# DSO_Clock.net
KiCad netlist of a schematic drawn in Altium Designer
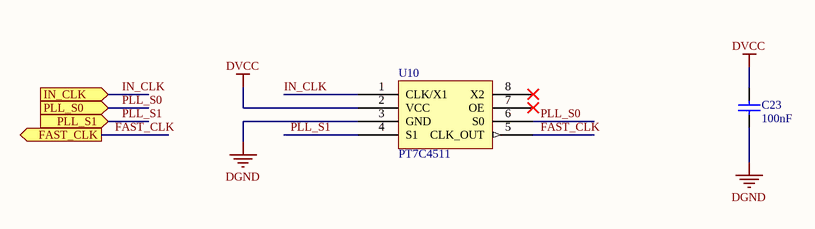
[diagram p0: DSO_Clock.SchDoc]

(export (version "E")
  (design (tool "Eeschema 10.0.6"))
  (components
    (comp (ref "C23")
      (value "100nF")
      (footprint "0805C")
      (description "Capacitor")
      (fields (field (name "REVIEWED BY") "RM - 2018/08/05"))
      (libsource (lib "DSO") (part "C"))
    )
    (comp (ref "U10")
      (value "PT7C4511")
      (footprint "SOIC-8")
      (description "PLL Clock Multiplier")
      (fields (field (name "REVIEWED BY") "RM - 2018/08/05"))
      (libsource (lib "DSO") (part "PT7C4511"))
    )
  )
  (nets
    (net (code "1") (name "/FAST_CLK") (class "Default")
      (node (ref "U10") (pin "5") (pinfunction "CLK_OUT_5") (pintype "output"))
    )
    (net (code "2") (name "/IN_CLK") (class "Default")
      (node (ref "U10") (pin "1") (pinfunction "CLK/X1_1") (pintype "passive"))
    )
    (net (code "3") (name "/PLL_S0") (class "Default")
      (node (ref "U10") (pin "6") (pinfunction "S0_6") (pintype "passive"))
    )
    (net (code "4") (name "/PLL_S1") (class "Default")
      (node (ref "U10") (pin "4") (pinfunction "S1_4") (pintype "passive"))
    )
    (net (code "5") (name "DGND") (class "Default")
      (node (ref "C23") (pin "2") (pinfunction "2_2") (pintype "passive"))
      (node (ref "U10") (pin "3") (pinfunction "GND_3") (pintype "passive"))
    )
    (net (code "6") (name "DVCC") (class "Default")
      (node (ref "C23") (pin "1") (pinfunction "1_1") (pintype "passive"))
      (node (ref "U10") (pin "2") (pinfunction "VCC_2") (pintype "passive"))
    )
    (net (code "7") (name "unconnected-(U10-OE-Pad7)") (class "Default")
      (node (ref "U10") (pin "7") (pinfunction "OE_7") (pintype "passive+no_connect"))
    )
    (net (code "8") (name "unconnected-(U10-X2-Pad8)") (class "Default")
      (node (ref "U10") (pin "8") (pinfunction "X2_8") (pintype "passive+no_connect"))
    )
  )
)
